# SpectrumAnalyzer.net
KiCad netlist of a schematic drawn in Altium Designer
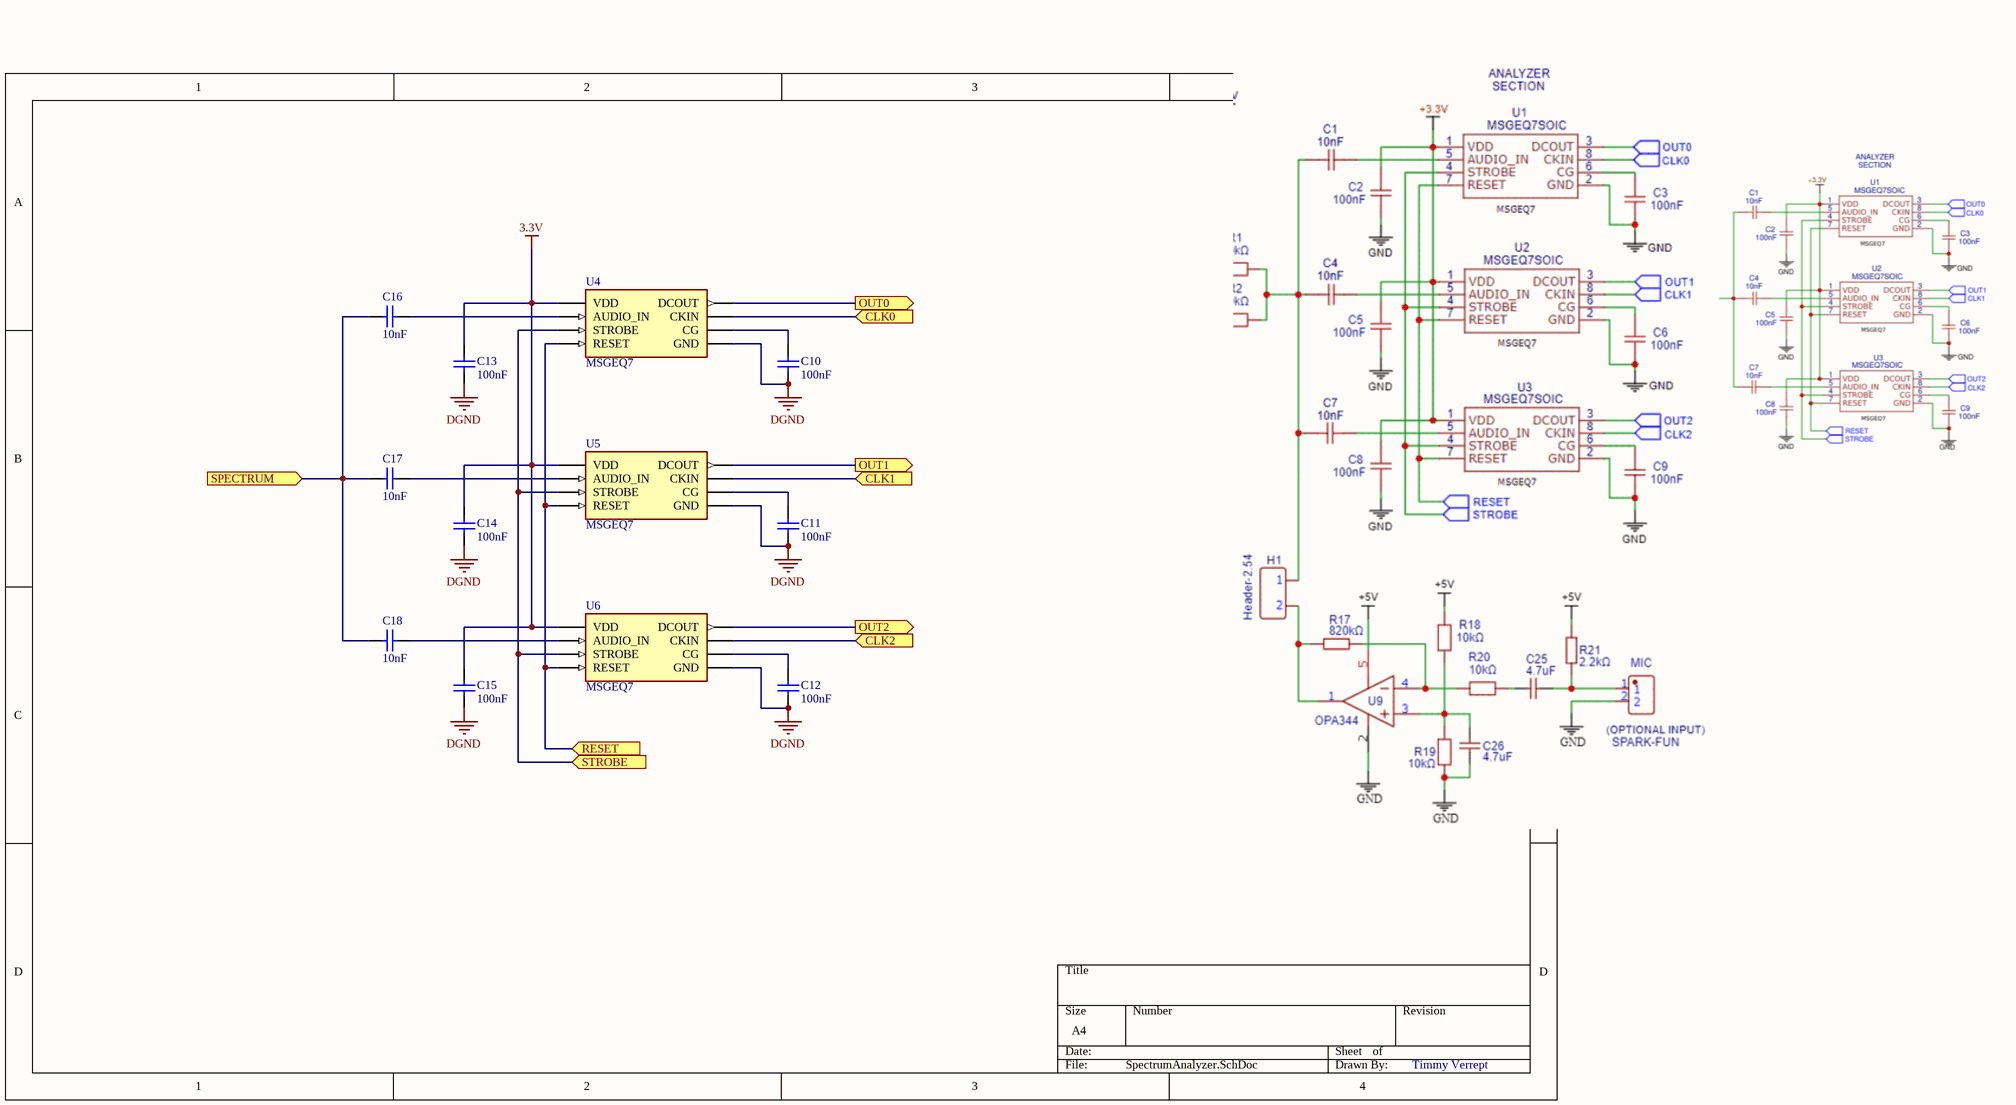
[diagram p0: SpectrumAnalyzer.SchDoc]

(export (version "E")
  (design (tool "Eeschema 10.0.6"))
  (components
    (comp (ref "C10")
      (value "100nF")
      (footprint "SMD_CAPACITOR")
      (fields (field (name "MANUFACTURER") "Vitramon") (field (name "PART NUMBER") "VJ0805Y682KXAMT"))
      (libsource (lib "Winnetrie_library") (part "CER Capacitor"))
    )
    (comp (ref "C11")
      (value "100nF")
      (footprint "SMD_CAPACITOR")
      (fields (field (name "MANUFACTURER") "Vitramon") (field (name "PART NUMBER") "VJ0805Y682KXAMT"))
      (libsource (lib "Winnetrie_library") (part "CER Capacitor"))
    )
    (comp (ref "C12")
      (value "100nF")
      (footprint "SMD_CAPACITOR")
      (fields (field (name "MANUFACTURER") "Vitramon") (field (name "PART NUMBER") "VJ0805Y682KXAMT"))
      (libsource (lib "Winnetrie_library") (part "CER Capacitor"))
    )
    (comp (ref "C13")
      (value "100nF")
      (footprint "SMD_CAPACITOR")
      (fields (field (name "MANUFACTURER") "Vitramon") (field (name "PART NUMBER") "VJ0805Y682KXAMT"))
      (libsource (lib "Winnetrie_library") (part "CER Capacitor"))
    )
    (comp (ref "C14")
      (value "100nF")
      (footprint "SMD_CAPACITOR")
      (fields (field (name "MANUFACTURER") "Vitramon") (field (name "PART NUMBER") "VJ0805Y682KXAMT"))
      (libsource (lib "Winnetrie_library") (part "CER Capacitor"))
    )
    (comp (ref "C15")
      (value "100nF")
      (footprint "SMD_CAPACITOR")
      (fields (field (name "MANUFACTURER") "Vitramon") (field (name "PART NUMBER") "VJ0805Y682KXAMT"))
      (libsource (lib "Winnetrie_library") (part "CER Capacitor"))
    )
    (comp (ref "C16")
      (value "10nF")
      (footprint "SMD_CAPACITOR")
      (fields (field (name "MANUFACTURER") "Vitramon") (field (name "PART NUMBER") "VJ0805Y682KXAMT"))
      (libsource (lib "Winnetrie_library") (part "CER Capacitor"))
    )
    (comp (ref "C17")
      (value "10nF")
      (footprint "SMD_CAPACITOR")
      (fields (field (name "MANUFACTURER") "Vitramon") (field (name "PART NUMBER") "VJ0805Y682KXAMT"))
      (libsource (lib "Winnetrie_library") (part "CER Capacitor"))
    )
    (comp (ref "C18")
      (value "10nF")
      (footprint "SMD_CAPACITOR")
      (fields (field (name "MANUFACTURER") "Vitramon") (field (name "PART NUMBER") "VJ0805Y682KXAMT"))
      (libsource (lib "Winnetrie_library") (part "CER Capacitor"))
    )
    (comp (ref "U4")
      (value "MSGEQ7")
      (footprint "MSGEQ7")
      (description "MSGEQ7 Signal Level Control Interface Arduino Platform Evaluation Expansion Board")
      (fields (field (name "MF") "SparkFun Electronics"))
      (libsource (lib "Winnetrie_library") (part "MSGEQ7"))
    )
    (comp (ref "U5")
      (value "MSGEQ7")
      (footprint "MSGEQ7")
      (description "MSGEQ7 Signal Level Control Interface Arduino Platform Evaluation Expansion Board")
      (fields (field (name "MF") "SparkFun Electronics"))
      (libsource (lib "Winnetrie_library") (part "MSGEQ7"))
    )
    (comp (ref "U6")
      (value "MSGEQ7")
      (footprint "MSGEQ7")
      (description "MSGEQ7 Signal Level Control Interface Arduino Platform Evaluation Expansion Board")
      (fields (field (name "MF") "SparkFun Electronics"))
      (libsource (lib "Winnetrie_library") (part "MSGEQ7"))
    )
  )
  (nets
    (net (code "1") (name "/CLK0") (class "Default")
      (node (ref "U4") (pin "8") (pinfunction "CKIN_8") (pintype "passive"))
    )
    (net (code "2") (name "/CLK1") (class "Default")
      (node (ref "U5") (pin "8") (pinfunction "CKIN_8") (pintype "passive"))
    )
    (net (code "3") (name "/CLK2") (class "Default")
      (node (ref "U6") (pin "8") (pinfunction "CKIN_8") (pintype "passive"))
    )
    (net (code "4") (name "/OUT0") (class "Default")
      (node (ref "U4") (pin "3") (pinfunction "DCOUT_3") (pintype "output"))
    )
    (net (code "5") (name "/OUT1") (class "Default")
      (node (ref "U5") (pin "3") (pinfunction "DCOUT_3") (pintype "output"))
    )
    (net (code "6") (name "/OUT2") (class "Default")
      (node (ref "U6") (pin "3") (pinfunction "DCOUT_3") (pintype "output"))
    )
    (net (code "7") (name "/RESET") (class "Default")
      (node (ref "U4") (pin "7") (pinfunction "RESET_7") (pintype "input"))
      (node (ref "U5") (pin "7") (pinfunction "RESET_7") (pintype "input"))
      (node (ref "U6") (pin "7") (pinfunction "RESET_7") (pintype "input"))
    )
    (net (code "8") (name "/SPECTRUM") (class "Default")
      (node (ref "C16") (pin "2") (pinfunction "2_2") (pintype "passive"))
      (node (ref "C17") (pin "2") (pinfunction "2_2") (pintype "passive"))
      (node (ref "C18") (pin "2") (pinfunction "2_2") (pintype "passive"))
    )
    (net (code "9") (name "/STROBE") (class "Default")
      (node (ref "U4") (pin "4") (pinfunction "STROBE_4") (pintype "input"))
      (node (ref "U5") (pin "4") (pinfunction "STROBE_4") (pintype "input"))
      (node (ref "U6") (pin "4") (pinfunction "STROBE_4") (pintype "input"))
    )
    (net (code "10") (name "3.3V") (class "Default")
      (node (ref "C13") (pin "2") (pinfunction "2_2") (pintype "passive"))
      (node (ref "C14") (pin "2") (pinfunction "2_2") (pintype "passive"))
      (node (ref "C15") (pin "2") (pinfunction "2_2") (pintype "passive"))
      (node (ref "U4") (pin "1") (pinfunction "VDD_1") (pintype "power_in"))
      (node (ref "U5") (pin "1") (pinfunction "VDD_1") (pintype "power_in"))
      (node (ref "U6") (pin "1") (pinfunction "VDD_1") (pintype "power_in"))
    )
    (net (code "11") (name "DGND") (class "Default")
      (node (ref "C10") (pin "1") (pinfunction "1_1") (pintype "passive"))
      (node (ref "C11") (pin "1") (pinfunction "1_1") (pintype "passive"))
      (node (ref "C12") (pin "1") (pinfunction "1_1") (pintype "passive"))
      (node (ref "C13") (pin "1") (pinfunction "1_1") (pintype "passive"))
      (node (ref "C14") (pin "1") (pinfunction "1_1") (pintype "passive"))
      (node (ref "C15") (pin "1") (pinfunction "1_1") (pintype "passive"))
      (node (ref "U4") (pin "2") (pinfunction "GND_2") (pintype "power_in"))
      (node (ref "U5") (pin "2") (pinfunction "GND_2") (pintype "power_in"))
      (node (ref "U6") (pin "2") (pinfunction "GND_2") (pintype "power_in"))
    )
    (net (code "12") (name "Net-(U4-AUDIO_IN)") (class "Default")
      (node (ref "C16") (pin "1") (pinfunction "1_1") (pintype "passive"))
      (node (ref "U4") (pin "5") (pinfunction "AUDIO_IN_5") (pintype "input"))
    )
    (net (code "13") (name "Net-(U4-CG)") (class "Default")
      (node (ref "C10") (pin "2") (pinfunction "2_2") (pintype "passive"))
      (node (ref "U4") (pin "6") (pinfunction "CG_6") (pintype "passive"))
    )
    (net (code "14") (name "Net-(U5-AUDIO_IN)") (class "Default")
      (node (ref "C17") (pin "1") (pinfunction "1_1") (pintype "passive"))
      (node (ref "U5") (pin "5") (pinfunction "AUDIO_IN_5") (pintype "input"))
    )
    (net (code "15") (name "Net-(U5-CG)") (class "Default")
      (node (ref "C11") (pin "2") (pinfunction "2_2") (pintype "passive"))
      (node (ref "U5") (pin "6") (pinfunction "CG_6") (pintype "passive"))
    )
    (net (code "16") (name "Net-(U6-AUDIO_IN)") (class "Default")
      (node (ref "C18") (pin "1") (pinfunction "1_1") (pintype "passive"))
      (node (ref "U6") (pin "5") (pinfunction "AUDIO_IN_5") (pintype "input"))
    )
    (net (code "17") (name "Net-(U6-CG)") (class "Default")
      (node (ref "C12") (pin "2") (pinfunction "2_2") (pintype "passive"))
      (node (ref "U6") (pin "6") (pinfunction "CG_6") (pintype "passive"))
    )
  )
)
